# Mosfet.net
KiCad netlist of a schematic drawn in EAGLE
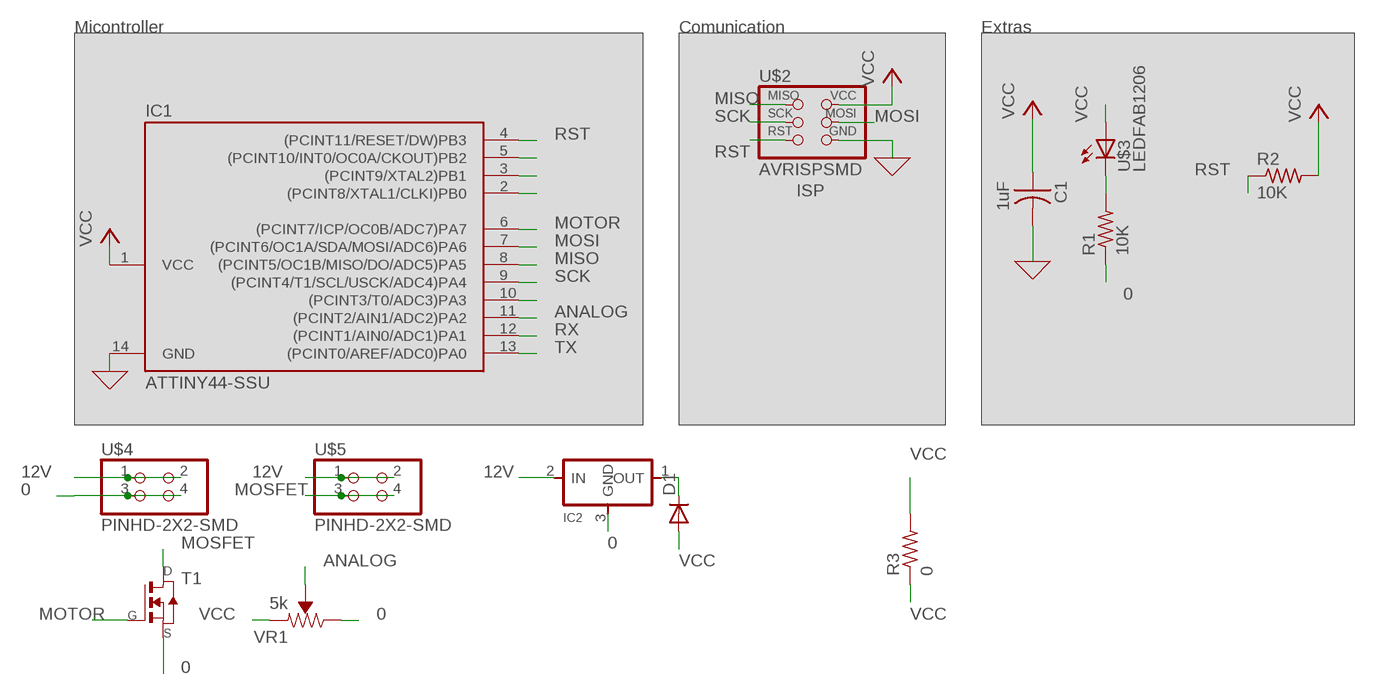
[diagram p0: schematic, sheet 1]

(export (version "E")
  (design (tool "Eeschema 10.0.6"))
  (components
    (comp (ref "C1")
      (value "1uF")
      (footprint "eagle-import:C1206FAB")
      (libsource (lib "eagle-import") (part "CAP-US1206FAB"))
    )
    (comp (ref "D1")
      (value "DIODESOD123")
      (footprint "eagle-import:SOD123")
      (libsource (lib "eagle-import") (part "DIODESOD123"))
    )
    (comp (ref "IC1")
      (value "ATTINY44-SSU")
      (footprint "eagle-import:SOIC14")
      (libsource (lib "eagle-import") (part "ATTINY44-SSU"))
    )
    (comp (ref "IC2")
      (value "REGULATORSOT23")
      (footprint "eagle-import:SOT23")
      (libsource (lib "eagle-import") (part "REGULATORSOT23"))
    )
    (comp (ref "R1")
      (value "10K")
      (footprint "eagle-import:R1206FAB")
      (libsource (lib "eagle-import") (part "RES-US1206FAB"))
    )
    (comp (ref "R2")
      (value "10K")
      (footprint "eagle-import:R1206FAB")
      (libsource (lib "eagle-import") (part "RES-US1206FAB"))
    )
    (comp (ref "R3")
      (value "0")
      (footprint "eagle-import:R1206FAB")
      (libsource (lib "eagle-import") (part "RES-US1206FAB"))
    )
    (comp (ref "T1")
      (value "NMOSFETSOT23")
      (footprint "eagle-import:SOT-23")
      (libsource (lib "eagle-import") (part "NMOSFETSOT23"))
    )
    (comp (ref "U$2")
      (value "AVRISPSMD")
      (footprint "eagle-import:2X03SMD")
      (libsource (lib "eagle-import") (part "AVRISPSMD"))
    )
    (comp (ref "U$3")
      (value "LEDFAB1206")
      (footprint "eagle-import:LED1206FAB")
      (libsource (lib "eagle-import") (part "LEDFAB1206"))
    )
    (comp (ref "U$4")
      (value "PINHD-2X2-SMD")
      (footprint "eagle-import:2X02SMD")
      (libsource (lib "eagle-import") (part "PINHD-2X2-SMD"))
    )
    (comp (ref "U$5")
      (value "PINHD-2X2-SMD")
      (footprint "eagle-import:2X02SMD")
      (libsource (lib "eagle-import") (part "PINHD-2X2-SMD"))
    )
    (comp (ref "VR1")
      (value "5k")
      (footprint "eagle-import:TRIMPOT-SMD-5MM")
      (libsource (lib "eagle-import") (part "TRIMPOT-SMD-5MM-CLOSED-1/4W-20%"))
    )
  )
  (nets
    (net (code "1") (name "/12V") (class "Default")
      (node (ref "IC2") (pin "2") (pinfunction "IN_2") (pintype "bidirectional"))
      (node (ref "U$4") (pin "1") (pinfunction "1_1") (pintype "passive"))
      (node (ref "U$4") (pin "2") (pinfunction "2_2") (pintype "passive"))
      (node (ref "U$5") (pin "1") (pinfunction "1_1") (pintype "passive"))
      (node (ref "U$5") (pin "2") (pinfunction "2_2") (pintype "passive"))
    )
    (net (code "2") (name "/ANALOG") (class "Default")
      (node (ref "IC1") (pin "11") (pinfunction "(PCINT2/AIN1/ADC2)PA2_11") (pintype "bidirectional"))
      (node (ref "VR1") (pin "B") (pinfunction "WIPER_B") (pintype "passive"))
    )
    (net (code "3") (name "/MISO") (class "Default")
      (node (ref "IC1") (pin "8") (pinfunction "(PCINT5/OC1B/MISO/DO/ADC5)PA5_8") (pintype "bidirectional"))
      (node (ref "U$2") (pin "1") (pinfunction "MISO_1") (pintype "passive"))
    )
    (net (code "4") (name "/MOSFET") (class "Default")
      (node (ref "T1") (pin "1") (pinfunction "D_1") (pintype "passive"))
      (node (ref "U$5") (pin "3") (pinfunction "3_3") (pintype "passive"))
      (node (ref "U$5") (pin "4") (pinfunction "4_4") (pintype "passive"))
    )
    (net (code "5") (name "/MOSI") (class "Default")
      (node (ref "IC1") (pin "7") (pinfunction "(PCINT6/OC1A/SDA/MOSI/ADC6)PA6_7") (pintype "bidirectional"))
      (node (ref "U$2") (pin "4") (pinfunction "MOSI_4") (pintype "passive"))
    )
    (net (code "6") (name "/MOTOR") (class "Default")
      (node (ref "IC1") (pin "6") (pinfunction "(PCINT7/ICP/OC0B/ADC7)PA7_6") (pintype "bidirectional"))
      (node (ref "T1") (pin "3") (pinfunction "G_3") (pintype "passive"))
    )
    (net (code "7") (name "/RST") (class "Default")
      (node (ref "IC1") (pin "4") (pinfunction "(PCINT11/RESET/DW)PB3_4") (pintype "bidirectional"))
      (node (ref "R2") (pin "1") (pinfunction "1_1") (pintype "passive"))
      (node (ref "U$2") (pin "5") (pinfunction "RST_5") (pintype "passive"))
    )
    (net (code "8") (name "/RX") (class "Default")
      (node (ref "IC1") (pin "12") (pinfunction "(PCINT1/AIN0/ADC1)PA1_12") (pintype "bidirectional"))
    )
    (net (code "9") (name "/SCK") (class "Default")
      (node (ref "IC1") (pin "9") (pinfunction "(PCINT4/T1/SCL/USCK/ADC4)PA4_9") (pintype "bidirectional"))
      (node (ref "U$2") (pin "3") (pinfunction "SCK_3") (pintype "passive"))
    )
    (net (code "10") (name "/TX") (class "Default")
      (node (ref "IC1") (pin "13") (pinfunction "(PCINT0/AREF/ADC0)PA0_13") (pintype "bidirectional"))
    )
    (net (code "11") (name "GND") (class "Default")
      (node (ref "C1") (pin "2") (pinfunction "2_2") (pintype "passive"))
      (node (ref "IC1") (pin "14") (pinfunction "GND_14") (pintype "power_in"))
      (node (ref "IC2") (pin "3") (pinfunction "GND_3") (pintype "bidirectional"))
      (node (ref "R1") (pin "1") (pinfunction "1_1") (pintype "passive"))
      (node (ref "T1") (pin "2") (pinfunction "S_2") (pintype "passive"))
      (node (ref "U$2") (pin "6") (pinfunction "GND_6") (pintype "passive"))
      (node (ref "U$4") (pin "3") (pinfunction "3_3") (pintype "passive"))
      (node (ref "U$4") (pin "4") (pinfunction "4_4") (pintype "passive"))
      (node (ref "VR1") (pin "C") (pinfunction "CW_C") (pintype "passive"))
    )
    (net (code "12") (name "Net-(D1-C)") (class "Default")
      (node (ref "D1") (pin "CATHODE") (pinfunction "C_CATHODE") (pintype "passive"))
      (node (ref "IC2") (pin "1") (pinfunction "OUT_1") (pintype "bidirectional"))
    )
    (net (code "13") (name "Net-(U$3-C)") (class "Default")
      (node (ref "R1") (pin "2") (pinfunction "2_2") (pintype "passive"))
      (node (ref "U$3") (pin "2") (pinfunction "C_2") (pintype "passive"))
    )
    (net (code "14") (name "VCC") (class "Default")
      (node (ref "C1") (pin "1") (pinfunction "1_1") (pintype "passive"))
      (node (ref "D1") (pin "ANODE") (pinfunction "A_ANODE") (pintype "passive"))
      (node (ref "IC1") (pin "1") (pinfunction "VCC_1") (pintype "power_in"))
      (node (ref "R2") (pin "2") (pinfunction "2_2") (pintype "passive"))
      (node (ref "R3") (pin "1") (pinfunction "1_1") (pintype "passive"))
      (node (ref "R3") (pin "2") (pinfunction "2_2") (pintype "passive"))
      (node (ref "U$2") (pin "2") (pinfunction "VCC_2") (pintype "passive"))
      (node (ref "U$3") (pin "1") (pinfunction "A_1") (pintype "passive"))
      (node (ref "VR1") (pin "A") (pinfunction "CCW_A") (pintype "passive"))
    )
    (net (code "15") (name "unconnected-(IC1-(PCINT3{slash}T0{slash}ADC3)PA3-Pad10)") (class "Default")
      (node (ref "IC1") (pin "10") (pinfunction "(PCINT3/T0/ADC3)PA3_10") (pintype "bidirectional"))
    )
    (net (code "16") (name "unconnected-(IC1-(PCINT8{slash}XTAL1{slash}CLKI)PB0-Pad2)") (class "Default")
      (node (ref "IC1") (pin "2") (pinfunction "(PCINT8/XTAL1/CLKI)PB0_2") (pintype "bidirectional"))
    )
    (net (code "17") (name "unconnected-(IC1-(PCINT9{slash}XTAL2)PB1-Pad3)") (class "Default")
      (node (ref "IC1") (pin "3") (pinfunction "(PCINT9/XTAL2)PB1_3") (pintype "bidirectional"))
    )
    (net (code "18") (name "unconnected-(IC1-(PCINT10{slash}INT0{slash}OC0A{slash}CKOUT)PB2-Pad5)") (class "Default")
      (node (ref "IC1") (pin "5") (pinfunction "(PCINT10/INT0/OC0A/CKOUT)PB2_5") (pintype "bidirectional"))
    )
  )
)
